# relay.net
KiCad netlist of a schematic drawn in Altium Designer
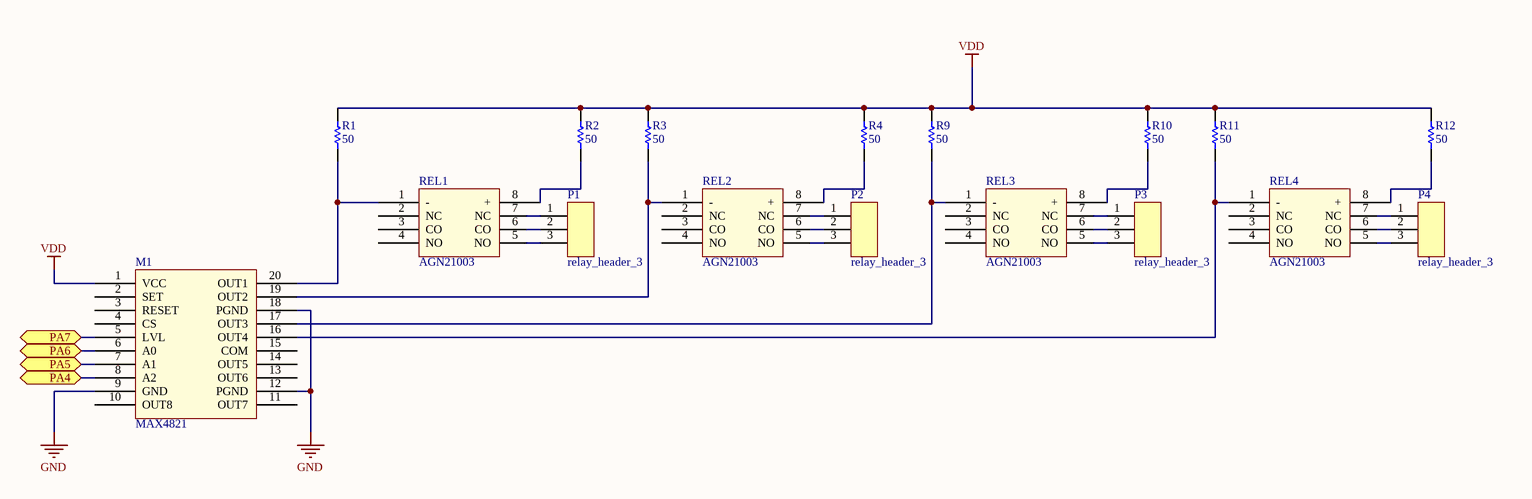
[diagram p0: relay.SchDoc]

(export (version "E")
  (design (tool "Eeschema 10.0.6"))
  (components
    (comp (ref "M1") (value "MAX4821") (footprint "TSSOP20") (libsource (lib "seeds") (part "MAX4821")))
    (comp (ref "P1")
      (value "relay_header_3")
      (footprint "relay_header_3")
      (libsource (lib "seeds") (part "relay_header_3"))
    )
    (comp (ref "P2")
      (value "relay_header_3")
      (footprint "relay_header_3")
      (libsource (lib "seeds") (part "relay_header_3"))
    )
    (comp (ref "P3")
      (value "relay_header_3")
      (footprint "relay_header_3")
      (libsource (lib "seeds") (part "relay_header_3"))
    )
    (comp (ref "P4")
      (value "relay_header_3")
      (footprint "relay_header_3")
      (libsource (lib "seeds") (part "relay_header_3"))
    )
    (comp (ref "R1")
      (value "50")
      (footprint "0603R")
      (description "Resistor")
      (fields (field (name "PUBLISHER") "Altium Limited"))
      (libsource (lib "MB1136") (part "Res1"))
    )
    (comp (ref "R2")
      (value "50")
      (footprint "0603R")
      (description "Resistor")
      (fields (field (name "PUBLISHER") "Altium Limited"))
      (libsource (lib "MB1136") (part "Res1"))
    )
    (comp (ref "R3")
      (value "50")
      (footprint "0603R")
      (description "Resistor")
      (fields (field (name "PUBLISHER") "Altium Limited"))
      (libsource (lib "MB1136") (part "Res1"))
    )
    (comp (ref "R4")
      (value "50")
      (footprint "0603R")
      (description "Resistor")
      (fields (field (name "PUBLISHER") "Altium Limited"))
      (libsource (lib "MB1136") (part "Res1"))
    )
    (comp (ref "R9")
      (value "50")
      (footprint "0603R")
      (description "Resistor")
      (fields (field (name "PUBLISHER") "Altium Limited"))
      (libsource (lib "MB1136") (part "Res1"))
    )
    (comp (ref "R10")
      (value "50")
      (footprint "0603R")
      (description "Resistor")
      (fields (field (name "PUBLISHER") "Altium Limited"))
      (libsource (lib "MB1136") (part "Res1"))
    )
    (comp (ref "R11")
      (value "50")
      (footprint "0603R")
      (description "Resistor")
      (fields (field (name "PUBLISHER") "Altium Limited"))
      (libsource (lib "MB1136") (part "Res1"))
    )
    (comp (ref "R12")
      (value "50")
      (footprint "0603R")
      (description "Resistor")
      (fields (field (name "PUBLISHER") "Altium Limited"))
      (libsource (lib "MB1136") (part "Res1"))
    )
    (comp (ref "REL1") (value "AGN21003") (footprint "AGN21003") (libsource (lib "seeds") (part "AGN21003")))
    (comp (ref "REL2") (value "AGN21003") (footprint "AGN21003") (libsource (lib "seeds") (part "AGN21003")))
    (comp (ref "REL3") (value "AGN21003") (footprint "AGN21003") (libsource (lib "seeds") (part "AGN21003")))
    (comp (ref "REL4") (value "AGN21003") (footprint "AGN21003") (libsource (lib "seeds") (part "AGN21003")))
  )
  (nets
    (net (code "1") (name "/PA4") (class "Default")
      (node (ref "M1") (pin "8") (pinfunction "A2_8") (pintype "passive"))
    )
    (net (code "2") (name "/PA5") (class "Default")
      (node (ref "M1") (pin "7") (pinfunction "A1_7") (pintype "passive"))
    )
    (net (code "3") (name "/PA6") (class "Default")
      (node (ref "M1") (pin "6") (pinfunction "A0_6") (pintype "passive"))
    )
    (net (code "4") (name "/PA7") (class "Default")
      (node (ref "M1") (pin "5") (pinfunction "LVL_5") (pintype "passive"))
    )
    (net (code "5") (name "GND") (class "Default")
      (node (ref "M1") (pin "12") (pinfunction "PGND_12") (pintype "passive"))
      (node (ref "M1") (pin "18") (pinfunction "PGND_18") (pintype "passive"))
      (node (ref "M1") (pin "9") (pinfunction "GND_9") (pintype "passive"))
    )
    (net (code "6") (name "Net-(M1-OUT1)") (class "Default")
      (node (ref "M1") (pin "20") (pinfunction "OUT1_20") (pintype "passive"))
      (node (ref "R1") (pin "2") (pinfunction "2_2") (pintype "passive"))
      (node (ref "REL1") (pin "1") (pinfunction "-_1") (pintype "passive"))
    )
    (net (code "7") (name "Net-(M1-OUT2)") (class "Default")
      (node (ref "M1") (pin "19") (pinfunction "OUT2_19") (pintype "passive"))
      (node (ref "R3") (pin "2") (pinfunction "2_2") (pintype "passive"))
      (node (ref "REL2") (pin "1") (pinfunction "-_1") (pintype "passive"))
    )
    (net (code "8") (name "Net-(M1-OUT3)") (class "Default")
      (node (ref "M1") (pin "17") (pinfunction "OUT3_17") (pintype "passive"))
      (node (ref "R9") (pin "2") (pinfunction "2_2") (pintype "passive"))
      (node (ref "REL3") (pin "1") (pinfunction "-_1") (pintype "passive"))
    )
    (net (code "9") (name "Net-(M1-OUT4)") (class "Default")
      (node (ref "M1") (pin "16") (pinfunction "OUT4_16") (pintype "passive"))
      (node (ref "R11") (pin "2") (pinfunction "2_2") (pintype "passive"))
      (node (ref "REL4") (pin "1") (pinfunction "-_1") (pintype "passive"))
    )
    (net (code "10") (name "Net-(P1-Pad1)") (class "Default")
      (node (ref "P1") (pin "1") (pintype "power_in"))
      (node (ref "REL1") (pin "7") (pinfunction "NC_7") (pintype "passive"))
    )
    (net (code "11") (name "Net-(P1-Pad2)") (class "Default")
      (node (ref "P1") (pin "2") (pintype "power_in"))
      (node (ref "REL1") (pin "6") (pinfunction "CO_6") (pintype "passive"))
    )
    (net (code "12") (name "Net-(P1-Pad3)") (class "Default")
      (node (ref "P1") (pin "3") (pintype "power_in"))
      (node (ref "REL1") (pin "5") (pinfunction "NO_5") (pintype "passive"))
    )
    (net (code "13") (name "Net-(P2-Pad1)") (class "Default")
      (node (ref "P2") (pin "1") (pintype "power_in"))
      (node (ref "REL2") (pin "7") (pinfunction "NC_7") (pintype "passive"))
    )
    (net (code "14") (name "Net-(P2-Pad2)") (class "Default")
      (node (ref "P2") (pin "2") (pintype "power_in"))
      (node (ref "REL2") (pin "6") (pinfunction "CO_6") (pintype "passive"))
    )
    (net (code "15") (name "Net-(P2-Pad3)") (class "Default")
      (node (ref "P2") (pin "3") (pintype "power_in"))
      (node (ref "REL2") (pin "5") (pinfunction "NO_5") (pintype "passive"))
    )
    (net (code "16") (name "Net-(P3-Pad1)") (class "Default")
      (node (ref "P3") (pin "1") (pintype "power_in"))
      (node (ref "REL3") (pin "7") (pinfunction "NC_7") (pintype "passive"))
    )
    (net (code "17") (name "Net-(P3-Pad2)") (class "Default")
      (node (ref "P3") (pin "2") (pintype "power_in"))
      (node (ref "REL3") (pin "6") (pinfunction "CO_6") (pintype "passive"))
    )
    (net (code "18") (name "Net-(P3-Pad3)") (class "Default")
      (node (ref "P3") (pin "3") (pintype "power_in"))
      (node (ref "REL3") (pin "5") (pinfunction "NO_5") (pintype "passive"))
    )
    (net (code "19") (name "Net-(P4-Pad1)") (class "Default")
      (node (ref "P4") (pin "1") (pintype "power_in"))
      (node (ref "REL4") (pin "7") (pinfunction "NC_7") (pintype "passive"))
    )
    (net (code "20") (name "Net-(P4-Pad2)") (class "Default")
      (node (ref "P4") (pin "2") (pintype "power_in"))
      (node (ref "REL4") (pin "6") (pinfunction "CO_6") (pintype "passive"))
    )
    (net (code "21") (name "Net-(P4-Pad3)") (class "Default")
      (node (ref "P4") (pin "3") (pintype "power_in"))
      (node (ref "REL4") (pin "5") (pinfunction "NO_5") (pintype "passive"))
    )
    (net (code "22") (name "Net-(REL1-+)") (class "Default")
      (node (ref "R2") (pin "2") (pinfunction "2_2") (pintype "passive"))
      (node (ref "REL1") (pin "8") (pinfunction "+_8") (pintype "passive"))
    )
    (net (code "23") (name "Net-(REL2-+)") (class "Default")
      (node (ref "R4") (pin "2") (pinfunction "2_2") (pintype "passive"))
      (node (ref "REL2") (pin "8") (pinfunction "+_8") (pintype "passive"))
    )
    (net (code "24") (name "Net-(REL3-+)") (class "Default")
      (node (ref "R10") (pin "2") (pinfunction "2_2") (pintype "passive"))
      (node (ref "REL3") (pin "8") (pinfunction "+_8") (pintype "passive"))
    )
    (net (code "25") (name "Net-(REL4-+)") (class "Default")
      (node (ref "R12") (pin "2") (pinfunction "2_2") (pintype "passive"))
      (node (ref "REL4") (pin "8") (pinfunction "+_8") (pintype "passive"))
    )
    (net (code "26") (name "VDD") (class "Default")
      (node (ref "M1") (pin "1") (pinfunction "VCC_1") (pintype "passive"))
      (node (ref "R1") (pin "1") (pinfunction "1_1") (pintype "passive"))
      (node (ref "R10") (pin "1") (pinfunction "1_1") (pintype "passive"))
      (node (ref "R11") (pin "1") (pinfunction "1_1") (pintype "passive"))
      (node (ref "R12") (pin "1") (pinfunction "1_1") (pintype "passive"))
      (node (ref "R2") (pin "1") (pinfunction "1_1") (pintype "passive"))
      (node (ref "R3") (pin "1") (pinfunction "1_1") (pintype "passive"))
      (node (ref "R4") (pin "1") (pinfunction "1_1") (pintype "passive"))
      (node (ref "R9") (pin "1") (pinfunction "1_1") (pintype "passive"))
    )
    (net (code "27") (name "unconnected-(M1-COM-Pad15)") (class "Default")
      (node (ref "M1") (pin "15") (pinfunction "COM_15") (pintype "passive"))
    )
    (net (code "28") (name "unconnected-(M1-CS-Pad4)") (class "Default")
      (node (ref "M1") (pin "4") (pinfunction "CS_4") (pintype "passive"))
    )
    (net (code "29") (name "unconnected-(M1-OUT5-Pad14)") (class "Default")
      (node (ref "M1") (pin "14") (pinfunction "OUT5_14") (pintype "passive"))
    )
    (net (code "30") (name "unconnected-(M1-OUT6-Pad13)") (class "Default")
      (node (ref "M1") (pin "13") (pinfunction "OUT6_13") (pintype "passive"))
    )
    (net (code "31") (name "unconnected-(M1-OUT7-Pad11)") (class "Default")
      (node (ref "M1") (pin "11") (pinfunction "OUT7_11") (pintype "passive"))
    )
    (net (code "32") (name "unconnected-(M1-OUT8-Pad10)") (class "Default")
      (node (ref "M1") (pin "10") (pinfunction "OUT8_10") (pintype "passive"))
    )
    (net (code "33") (name "unconnected-(M1-RESET-Pad3)") (class "Default")
      (node (ref "M1") (pin "3") (pinfunction "RESET_3") (pintype "passive"))
    )
    (net (code "34") (name "unconnected-(M1-SET-Pad2)") (class "Default")
      (node (ref "M1") (pin "2") (pinfunction "SET_2") (pintype "passive"))
    )
    (net (code "35") (name "unconnected-(REL1-CO-Pad3)") (class "Default")
      (node (ref "REL1") (pin "3") (pinfunction "CO_3") (pintype "passive"))
    )
    (net (code "36") (name "unconnected-(REL1-NC-Pad2)") (class "Default")
      (node (ref "REL1") (pin "2") (pinfunction "NC_2") (pintype "passive"))
    )
    (net (code "37") (name "unconnected-(REL1-NO-Pad4)") (class "Default")
      (node (ref "REL1") (pin "4") (pinfunction "NO_4") (pintype "passive"))
    )
    (net (code "38") (name "unconnected-(REL2-CO-Pad3)") (class "Default")
      (node (ref "REL2") (pin "3") (pinfunction "CO_3") (pintype "passive"))
    )
    (net (code "39") (name "unconnected-(REL2-NC-Pad2)") (class "Default")
      (node (ref "REL2") (pin "2") (pinfunction "NC_2") (pintype "passive"))
    )
    (net (code "40") (name "unconnected-(REL2-NO-Pad4)") (class "Default")
      (node (ref "REL2") (pin "4") (pinfunction "NO_4") (pintype "passive"))
    )
    (net (code "41") (name "unconnected-(REL3-CO-Pad3)") (class "Default")
      (node (ref "REL3") (pin "3") (pinfunction "CO_3") (pintype "passive"))
    )
    (net (code "42") (name "unconnected-(REL3-NC-Pad2)") (class "Default")
      (node (ref "REL3") (pin "2") (pinfunction "NC_2") (pintype "passive"))
    )
    (net (code "43") (name "unconnected-(REL3-NO-Pad4)") (class "Default")
      (node (ref "REL3") (pin "4") (pinfunction "NO_4") (pintype "passive"))
    )
    (net (code "44") (name "unconnected-(REL4-CO-Pad3)") (class "Default")
      (node (ref "REL4") (pin "3") (pinfunction "CO_3") (pintype "passive"))
    )
    (net (code "45") (name "unconnected-(REL4-NC-Pad2)") (class "Default")
      (node (ref "REL4") (pin "2") (pinfunction "NC_2") (pintype "passive"))
    )
    (net (code "46") (name "unconnected-(REL4-NO-Pad4)") (class "Default")
      (node (ref "REL4") (pin "4") (pinfunction "NO_4") (pintype "passive"))
    )
  )
)
